# single_channel_-_Rev_B_-_Part_2.net
KiCad netlist of a schematic drawn in EAGLE
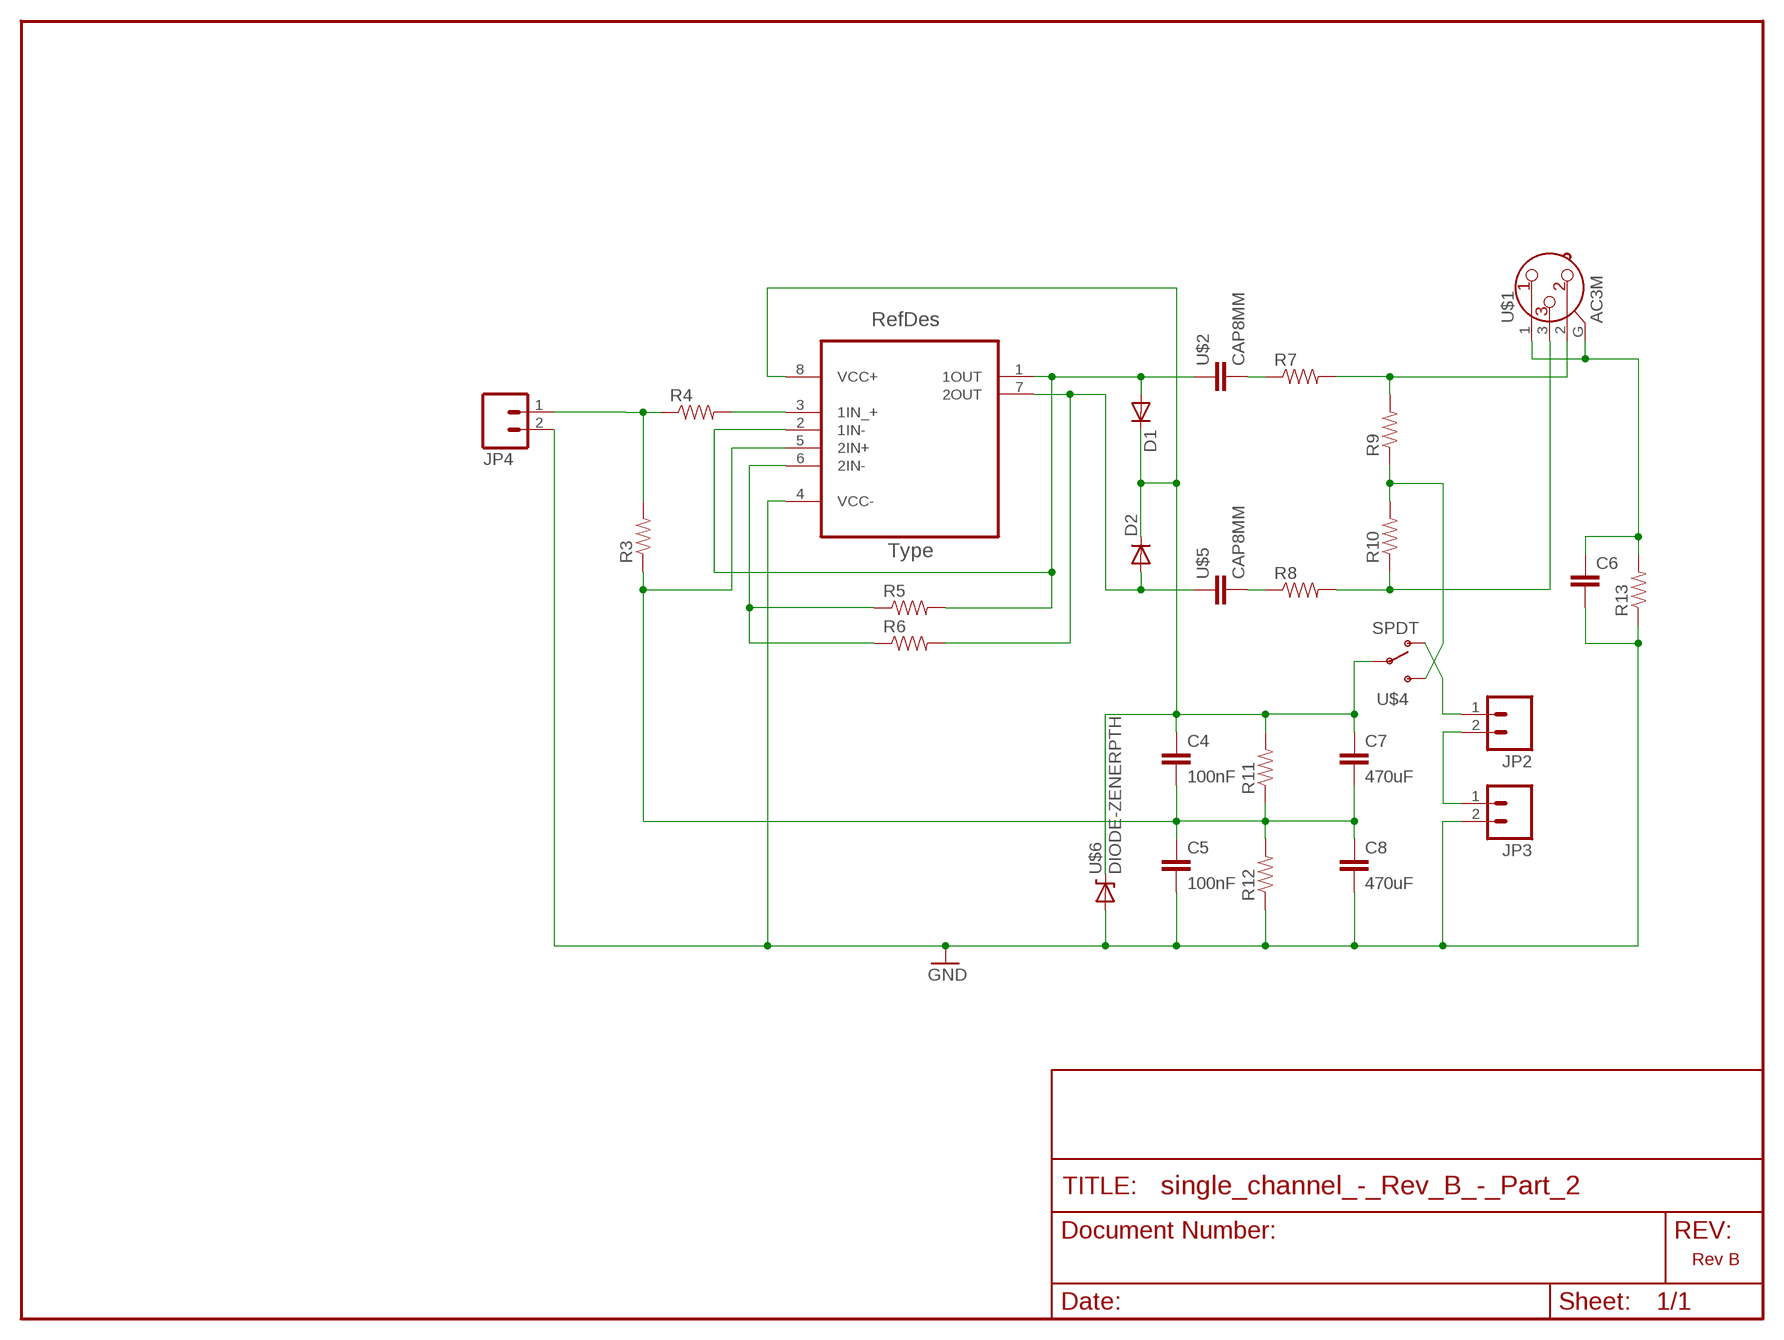
[diagram p0: schematic, sheet 1]

(export (version "E")
  (design (tool "Eeschema 10.0.6"))
  (components
    (comp (ref "C4")
      (value "100nF")
      (footprint "eagle-import:CAP-PTH-5MM")
      (libsource (lib "eagle-import") (part "CAPPTH1"))
    )
    (comp (ref "C5")
      (value "100nF")
      (footprint "eagle-import:CAP-PTH-5MM")
      (libsource (lib "eagle-import") (part "CAPPTH1"))
    )
    (comp (ref "C6")
      (value "CAPPTH1")
      (footprint "eagle-import:CAP-PTH-5MM")
      (libsource (lib "eagle-import") (part "CAPPTH1"))
    )
    (comp (ref "C7")
      (value "470uF")
      (footprint "eagle-import:CAP-PTH-5MM")
      (libsource (lib "eagle-import") (part "SparkFun-Passives_CAPPTH1"))
    )
    (comp (ref "C8")
      (value "470uF")
      (footprint "eagle-import:CAP-PTH-5MM")
      (libsource (lib "eagle-import") (part "SparkFun-Passives_CAPPTH1"))
    )
    (comp (ref "D1")
      (value "DIODE1N4148")
      (footprint "eagle-import:DIODE-1N4148")
      (libsource (lib "eagle-import") (part "DIODE1N4148"))
    )
    (comp (ref "D2")
      (value "DIODE1N4148")
      (footprint "eagle-import:DIODE-1N4148")
      (libsource (lib "eagle-import") (part "DIODE1N4148"))
    )
    (comp (ref "JP2")
      (value "M02PTH3")
      (footprint "eagle-import:1X02_LONGPADS")
      (libsource (lib "eagle-import") (part "M02PTH3"))
    )
    (comp (ref "JP3")
      (value "M02PTH3")
      (footprint "eagle-import:1X02_LONGPADS")
      (libsource (lib "eagle-import") (part "M02PTH3"))
    )
    (comp (ref "JP4")
      (value "M02PTH3")
      (footprint "eagle-import:1X02_LONGPADS")
      (libsource (lib "eagle-import") (part "M02PTH3"))
    )
    (comp (ref "R3")
      (value "RESISTORPTH-1/2W")
      (footprint "eagle-import:AXIAL-0.5")
      (libsource (lib "eagle-import") (part "RESISTORPTH-1/2W"))
    )
    (comp (ref "R4")
      (value "RESISTORPTH-1/2W")
      (footprint "eagle-import:AXIAL-0.5")
      (libsource (lib "eagle-import") (part "RESISTORPTH-1/2W"))
    )
    (comp (ref "R5")
      (value "RESISTORPTH-1/2W")
      (footprint "eagle-import:AXIAL-0.5")
      (libsource (lib "eagle-import") (part "RESISTORPTH-1/2W"))
    )
    (comp (ref "R6")
      (value "RESISTORPTH-1/2W")
      (footprint "eagle-import:AXIAL-0.5")
      (libsource (lib "eagle-import") (part "RESISTORPTH-1/2W"))
    )
    (comp (ref "R7")
      (value "RESISTORPTH-1/2W")
      (footprint "eagle-import:AXIAL-0.5")
      (libsource (lib "eagle-import") (part "RESISTORPTH-1/2W"))
    )
    (comp (ref "R8")
      (value "RESISTORPTH-1/2W")
      (footprint "eagle-import:AXIAL-0.5")
      (libsource (lib "eagle-import") (part "RESISTORPTH-1/2W"))
    )
    (comp (ref "R9")
      (value "RESISTORPTH-1/2W")
      (footprint "eagle-import:AXIAL-0.5")
      (libsource (lib "eagle-import") (part "RESISTORPTH-1/2W"))
    )
    (comp (ref "R10")
      (value "RESISTORPTH-1/2W")
      (footprint "eagle-import:AXIAL-0.5")
      (libsource (lib "eagle-import") (part "RESISTORPTH-1/2W"))
    )
    (comp (ref "R11")
      (value "RESISTORPTH-1/2W")
      (footprint "eagle-import:AXIAL-0.5")
      (libsource (lib "eagle-import") (part "RESISTORPTH-1/2W"))
    )
    (comp (ref "R12")
      (value "RESISTORPTH-1/2W")
      (footprint "eagle-import:AXIAL-0.5")
      (libsource (lib "eagle-import") (part "RESISTORPTH-1/2W"))
    )
    (comp (ref "R13")
      (value "RESISTORPTH-1/2W")
      (footprint "eagle-import:AXIAL-0.5")
      (libsource (lib "eagle-import") (part "RESISTORPTH-1/2W"))
    )
    (comp (ref "U$1")
      (value "AC3M")
      (footprint "eagle-import:AC3MAH")
      (libsource (lib "eagle-import") (part "AC3M"))
    )
    (comp (ref "U$2")
      (value "CAP8MM")
      (footprint "eagle-import:8MM")
      (libsource (lib "eagle-import") (part "CAP8MM"))
    )
    (comp (ref "U$4")
      (value "SPDT")
      (footprint "eagle-import:SPDT-SLIDE")
      (libsource (lib "eagle-import") (part "SPDT"))
    )
    (comp (ref "U$5")
      (value "CAP8MM")
      (footprint "eagle-import:8MM")
      (libsource (lib "eagle-import") (part "CAP8MM"))
    )
    (comp (ref "U$6")
      (value "DIODE-ZENERPTH")
      (footprint "eagle-import:DIODE-ZENER")
      (libsource (lib "eagle-import") (part "DIODE-ZENERPTH"))
    )
    (comp (ref "U1")
      (value "TL072CP")
      (footprint "eagle-import:DIP254P762X508-8")
      (libsource (lib "eagle-import") (part "TL072CP"))
    )
  )
  (nets
    (net (code "1") (name "GND") (class "Default")
      (node (ref "C5") (pin "2") (pinfunction "2_2") (pintype "passive"))
      (node (ref "C6") (pin "2") (pinfunction "2_2") (pintype "passive"))
      (node (ref "C8") (pin "2") (pinfunction "2_2") (pintype "passive"))
      (node (ref "JP3") (pin "2") (pinfunction "2_2") (pintype "passive"))
      (node (ref "JP4") (pin "2") (pinfunction "2_2") (pintype "passive"))
      (node (ref "R12") (pin "P$1") (pinfunction "1_P$1") (pintype "passive"))
      (node (ref "R13") (pin "P$1") (pinfunction "1_P$1") (pintype "passive"))
      (node (ref "U$6") (pin "P$2") (pinfunction "A_P$2") (pintype "passive"))
      (node (ref "U1") (pin "4") (pinfunction "VCC-_4") (pintype "passive"))
    )
    (net (code "2") (name "Net-(JP2-Pad1)") (class "Default")
      (node (ref "JP2") (pin "1") (pinfunction "1_1") (pintype "passive"))
      (node (ref "U$4") (pin "1") (pinfunction "1_1") (pintype "passive"))
    )
    (net (code "3") (name "Net-(JP2-Pad2)") (class "Default")
      (node (ref "JP2") (pin "2") (pinfunction "2_2") (pintype "passive"))
      (node (ref "JP3") (pin "1") (pinfunction "1_1") (pintype "passive"))
    )
    (net (code "4") (name "Net-(R3-2)") (class "Default")
      (node (ref "JP4") (pin "1") (pinfunction "1_1") (pintype "passive"))
      (node (ref "R3") (pin "P$2") (pinfunction "2_P$2") (pintype "passive"))
      (node (ref "R4") (pin "P$1") (pinfunction "1_P$1") (pintype "passive"))
    )
    (net (code "5") (name "Net-(R4-2)") (class "Default")
      (node (ref "R4") (pin "P$2") (pinfunction "2_P$2") (pintype "passive"))
      (node (ref "U1") (pin "3") (pinfunction "1IN_+_3") (pintype "input"))
    )
    (net (code "6") (name "Net-(R5-1)") (class "Default")
      (node (ref "R5") (pin "P$1") (pinfunction "1_P$1") (pintype "passive"))
      (node (ref "R6") (pin "P$1") (pinfunction "1_P$1") (pintype "passive"))
      (node (ref "U1") (pin "6") (pinfunction "2IN-_6") (pintype "input"))
    )
    (net (code "7") (name "Net-(R5-2)") (class "Default")
      (node (ref "D1") (pin "A") (pinfunction "A_A") (pintype "passive"))
      (node (ref "R5") (pin "P$2") (pinfunction "2_P$2") (pintype "passive"))
      (node (ref "U$2") (pin "P$1") (pinfunction "1_P$1") (pintype "passive"))
      (node (ref "U1") (pin "1") (pinfunction "1OUT_1") (pintype "output"))
      (node (ref "U1") (pin "2") (pinfunction "1IN-_2") (pintype "input"))
    )
    (net (code "8") (name "Net-(R6-2)") (class "Default")
      (node (ref "D2") (pin "A") (pinfunction "A_A") (pintype "passive"))
      (node (ref "R6") (pin "P$2") (pinfunction "2_P$2") (pintype "passive"))
      (node (ref "U$5") (pin "P$1") (pinfunction "1_P$1") (pintype "passive"))
      (node (ref "U1") (pin "7") (pinfunction "2OUT_7") (pintype "output"))
    )
    (net (code "9") (name "Net-(R7-1)") (class "Default")
      (node (ref "R7") (pin "P$1") (pinfunction "1_P$1") (pintype "passive"))
      (node (ref "U$2") (pin "P$2") (pinfunction "2_P$2") (pintype "passive"))
    )
    (net (code "10") (name "Net-(R7-2)") (class "Default")
      (node (ref "R7") (pin "P$2") (pinfunction "2_P$2") (pintype "passive"))
      (node (ref "R9") (pin "P$2") (pinfunction "2_P$2") (pintype "passive"))
      (node (ref "U$1") (pin "2") (pinfunction "2_2") (pintype "passive"))
    )
    (net (code "11") (name "Net-(R8-1)") (class "Default")
      (node (ref "R8") (pin "P$1") (pinfunction "1_P$1") (pintype "passive"))
      (node (ref "U$5") (pin "P$2") (pinfunction "2_P$2") (pintype "passive"))
    )
    (net (code "12") (name "Net-(R10-1)") (class "Default")
      (node (ref "R10") (pin "P$1") (pinfunction "1_P$1") (pintype "passive"))
      (node (ref "R8") (pin "P$2") (pinfunction "2_P$2") (pintype "passive"))
      (node (ref "U$1") (pin "3") (pinfunction "3_3") (pintype "passive"))
    )
    (net (code "13") (name "Net-(R10-2)") (class "Default")
      (node (ref "R10") (pin "P$2") (pinfunction "2_P$2") (pintype "passive"))
      (node (ref "R9") (pin "P$1") (pinfunction "1_P$1") (pintype "passive"))
      (node (ref "U$4") (pin "3") (pinfunction "3_3") (pintype "passive"))
    )
    (net (code "14") (name "Net-(R11-1)") (class "Default")
      (node (ref "C4") (pin "2") (pinfunction "2_2") (pintype "passive"))
      (node (ref "C5") (pin "1") (pinfunction "1_1") (pintype "passive"))
      (node (ref "C7") (pin "2") (pinfunction "2_2") (pintype "passive"))
      (node (ref "C8") (pin "1") (pinfunction "1_1") (pintype "passive"))
      (node (ref "R11") (pin "P$1") (pinfunction "1_P$1") (pintype "passive"))
      (node (ref "R12") (pin "P$2") (pinfunction "2_P$2") (pintype "passive"))
      (node (ref "R3") (pin "P$1") (pinfunction "1_P$1") (pintype "passive"))
      (node (ref "U1") (pin "5") (pinfunction "2IN+_5") (pintype "input"))
    )
    (net (code "15") (name "Net-(R11-2)") (class "Default")
      (node (ref "C4") (pin "1") (pinfunction "1_1") (pintype "passive"))
      (node (ref "C7") (pin "1") (pinfunction "1_1") (pintype "passive"))
      (node (ref "D1") (pin "C") (pinfunction "C_C") (pintype "passive"))
      (node (ref "D2") (pin "C") (pinfunction "C_C") (pintype "passive"))
      (node (ref "R11") (pin "P$2") (pinfunction "2_P$2") (pintype "passive"))
      (node (ref "U$4") (pin "2") (pinfunction "2_2") (pintype "passive"))
      (node (ref "U$6") (pin "P$1") (pinfunction "C_P$1") (pintype "passive"))
      (node (ref "U1") (pin "8") (pinfunction "VCC+_8") (pintype "power_in"))
    )
    (net (code "16") (name "Net-(R13-2)") (class "Default")
      (node (ref "C6") (pin "1") (pinfunction "1_1") (pintype "passive"))
      (node (ref "R13") (pin "P$2") (pinfunction "2_P$2") (pintype "passive"))
      (node (ref "U$1") (pin "1") (pinfunction "1_1") (pintype "passive"))
      (node (ref "U$1") (pin "G") (pinfunction "G_G") (pintype "passive"))
    )
  )
)
